# ir-sender.net
KiCad netlist of a schematic drawn in EAGLE
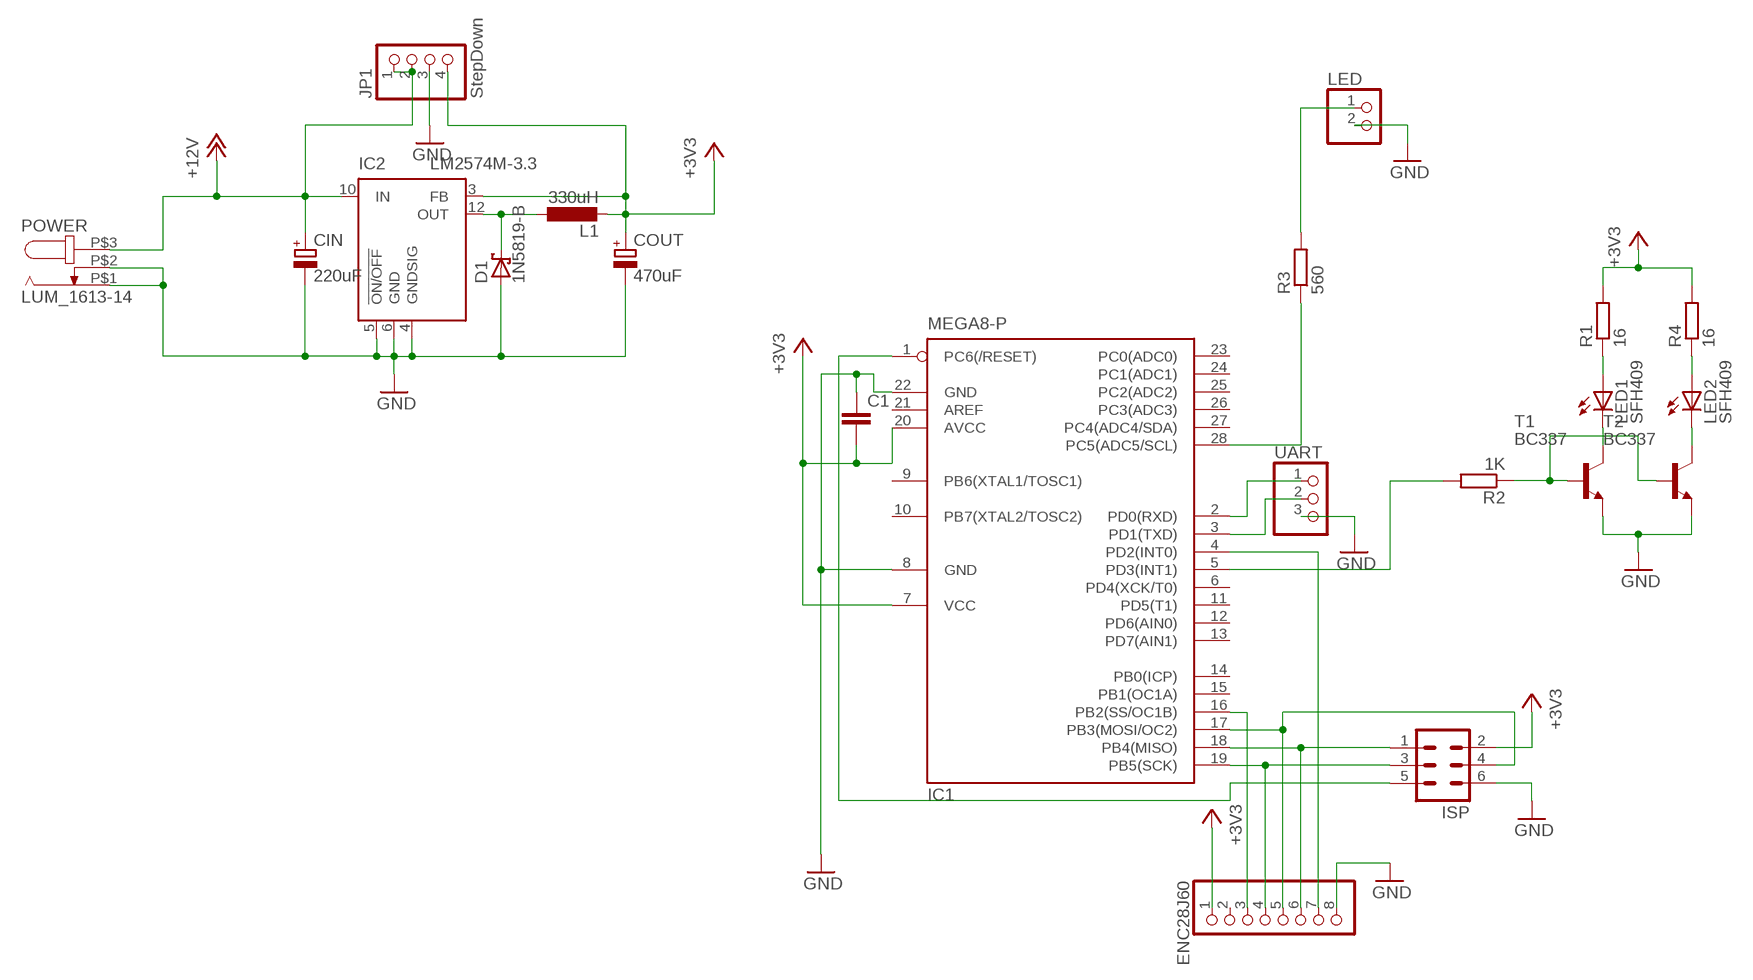
[diagram p0: schematic, sheet 1]

(export (version "E")
  (design (tool "Eeschema 10.0.6"))
  (components
    (comp (ref "C1")
      (value "C-EU025-030X050")
      (footprint "eagle-import:C025-030X050")
      (libsource (lib "eagle-import") (part "C-EU025-030X050"))
    )
    (comp (ref "CIN")
      (value "220uF")
      (footprint "eagle-import:E3,5-8")
      (libsource (lib "eagle-import") (part "CPOL-EUE3.5-8"))
    )
    (comp (ref "COUT")
      (value "470uF")
      (footprint "eagle-import:E5-10,5")
      (libsource (lib "eagle-import") (part "CPOL-EUE5-10.5"))
    )
    (comp (ref "D1")
      (value "1N5819-B")
      (footprint "eagle-import:DO41-7.6")
      (libsource (lib "eagle-import") (part "1N5819-B"))
    )
    (comp (ref "ENC28J60")
      (value "PINHD-1X8")
      (footprint "eagle-import:1X08")
      (libsource (lib "eagle-import") (part "PINHD-1X8"))
    )
    (comp (ref "IC1")
      (value "MEGA8-P")
      (footprint "eagle-import:DIL28-3")
      (libsource (lib "eagle-import") (part "MEGA8-P"))
    )
    (comp (ref "IC2")
      (value "LM2574M-3.3")
      (footprint "eagle-import:SO14W")
      (libsource (lib "eagle-import") (part "LM2574?-M3.3"))
    )
    (comp (ref "ISP")
      (value "ML6")
      (footprint "eagle-import:ML6")
      (libsource (lib "eagle-import") (part "ML6"))
    )
    (comp (ref "JP1")
      (value "StepDown")
      (footprint "eagle-import:1X04")
      (libsource (lib "eagle-import") (part "PINHD-1X4"))
    )
    (comp (ref "L1")
      (value "330uH")
      (footprint "eagle-import:PIS2816")
      (libsource (lib "eagle-import") (part "PIS4728"))
    )
    (comp (ref "LED")
      (value "PINHD-1X2")
      (footprint "eagle-import:1X02")
      (libsource (lib "eagle-import") (part "PINHD-1X2"))
    )
    (comp (ref "LED1")
      (value "SFH409")
      (footprint "eagle-import:SFH482")
      (libsource (lib "eagle-import") (part "LEDSFH482"))
    )
    (comp (ref "LED2")
      (value "SFH409")
      (footprint "eagle-import:SFH482")
      (libsource (lib "eagle-import") (part "LEDSFH482"))
    )
    (comp (ref "POWER")
      (value "LUM_1613-14")
      (footprint "eagle-import:DCJ0202")
      (libsource (lib "eagle-import") (part "LUM_1613-14"))
    )
    (comp (ref "R1")
      (value "16")
      (footprint "eagle-import:0207_7")
      (libsource (lib "eagle-import") (part "R-EU_0207/7"))
    )
    (comp (ref "R2")
      (value "1K")
      (footprint "eagle-import:0207_7")
      (libsource (lib "eagle-import") (part "R-EU_0207/7"))
    )
    (comp (ref "R3")
      (value "560")
      (footprint "eagle-import:0207_7")
      (libsource (lib "eagle-import") (part "R-EU_0207/7"))
    )
    (comp (ref "R4")
      (value "16")
      (footprint "eagle-import:0207_7")
      (libsource (lib "eagle-import") (part "R-EU_0207/7"))
    )
    (comp (ref "T1")
      (value "BC337")
      (footprint "eagle-import:TO92")
      (libsource (lib "eagle-import") (part "BC337"))
    )
    (comp (ref "T2")
      (value "BC337")
      (footprint "eagle-import:TO92")
      (libsource (lib "eagle-import") (part "BC337"))
    )
    (comp (ref "UART")
      (value "PINHD-1X3_2.54")
      (footprint "eagle-import:1X03")
      (libsource (lib "eagle-import") (part "PINHD-1X3_2.54"))
    )
  )
  (nets
    (net (code "1") (name "+3V3") (class "Default")
      (node (ref "C1") (pin "2") (pinfunction "2_2") (pintype "passive"))
      (node (ref "COUT") (pin "+") (pinfunction "+_+") (pintype "passive"))
      (node (ref "ENC28J60") (pin "1") (pinfunction "1_1") (pintype "passive"))
      (node (ref "IC1") (pin "20") (pinfunction "AVCC_20") (pintype "power_in"))
      (node (ref "IC1") (pin "7") (pinfunction "VCC_7") (pintype "power_in"))
      (node (ref "IC2") (pin "3") (pinfunction "FB_3") (pintype "input"))
      (node (ref "ISP") (pin "2") (pinfunction "2_2") (pintype "passive"))
      (node (ref "JP1") (pin "4") (pinfunction "4_4") (pintype "passive"))
      (node (ref "L1") (pin "2") (pinfunction "2_2") (pintype "passive"))
      (node (ref "R1") (pin "2") (pinfunction "2_2") (pintype "passive"))
      (node (ref "R4") (pin "2") (pinfunction "2_2") (pintype "passive"))
    )
    (net (code "2") (name "+12V") (class "Default")
      (node (ref "CIN") (pin "+") (pinfunction "+_+") (pintype "passive"))
      (node (ref "IC2") (pin "10") (pinfunction "IN_10") (pintype "input"))
      (node (ref "JP1") (pin "1") (pinfunction "1_1") (pintype "passive"))
      (node (ref "JP1") (pin "2") (pinfunction "2_2") (pintype "passive"))
      (node (ref "POWER") (pin "P$3") (pinfunction "3_P$3") (pintype "passive"))
    )
    (net (code "3") (name "GND") (class "Default")
      (node (ref "C1") (pin "1") (pinfunction "1_1") (pintype "passive"))
      (node (ref "CIN") (pin "-") (pinfunction "-_-") (pintype "passive"))
      (node (ref "COUT") (pin "-") (pinfunction "-_-") (pintype "passive"))
      (node (ref "D1") (pin "A") (pinfunction "A_A") (pintype "passive"))
      (node (ref "ENC28J60") (pin "8") (pinfunction "8_8") (pintype "passive"))
      (node (ref "IC1") (pin "22") (pinfunction "GND_22") (pintype "power_in"))
      (node (ref "IC1") (pin "8") (pinfunction "GND_8") (pintype "power_in"))
      (node (ref "IC2") (pin "4") (pinfunction "GNDSIG_4") (pintype "input"))
      (node (ref "IC2") (pin "5") (pinfunction "~{ON/OFF}_5") (pintype "input"))
      (node (ref "IC2") (pin "6") (pinfunction "GND_6") (pintype "power_in"))
      (node (ref "ISP") (pin "6") (pinfunction "6_6") (pintype "passive"))
      (node (ref "JP1") (pin "3") (pinfunction "3_3") (pintype "passive"))
      (node (ref "LED") (pin "2") (pinfunction "2_2") (pintype "passive"))
      (node (ref "POWER") (pin "P$1") (pinfunction "1_P$1") (pintype "passive"))
      (node (ref "POWER") (pin "P$2") (pinfunction "2_P$2") (pintype "passive"))
      (node (ref "T1") (pin "1") (pinfunction "E_1") (pintype "passive"))
      (node (ref "T2") (pin "1") (pinfunction "E_1") (pintype "passive"))
      (node (ref "UART") (pin "3") (pinfunction "3_3") (pintype "passive"))
    )
    (net (code "4") (name "Net-(IC1-PB2(SS{slash}OC1B))") (class "Default")
      (node (ref "ENC28J60") (pin "3") (pinfunction "3_3") (pintype "passive"))
      (node (ref "IC1") (pin "16") (pinfunction "PB2(SS/OC1B)_16") (pintype "bidirectional"))
    )
    (net (code "5") (name "Net-(IC1-PB3(MOSI{slash}OC2))") (class "Default")
      (node (ref "ENC28J60") (pin "5") (pinfunction "5_5") (pintype "passive"))
      (node (ref "IC1") (pin "17") (pinfunction "PB3(MOSI/OC2)_17") (pintype "bidirectional"))
      (node (ref "ISP") (pin "4") (pinfunction "4_4") (pintype "passive"))
    )
    (net (code "6") (name "Net-(IC1-PB4(MISO))") (class "Default")
      (node (ref "ENC28J60") (pin "6") (pinfunction "6_6") (pintype "passive"))
      (node (ref "IC1") (pin "18") (pinfunction "PB4(MISO)_18") (pintype "bidirectional"))
      (node (ref "ISP") (pin "1") (pinfunction "1_1") (pintype "passive"))
    )
    (net (code "7") (name "Net-(IC1-PB5(SCK))") (class "Default")
      (node (ref "ENC28J60") (pin "4") (pinfunction "4_4") (pintype "passive"))
      (node (ref "IC1") (pin "19") (pinfunction "PB5(SCK)_19") (pintype "bidirectional"))
      (node (ref "ISP") (pin "3") (pinfunction "3_3") (pintype "passive"))
    )
    (net (code "8") (name "Net-(IC1-PC5(ADC5{slash}SCL))") (class "Default")
      (node (ref "IC1") (pin "28") (pinfunction "PC5(ADC5/SCL)_28") (pintype "bidirectional"))
      (node (ref "R3") (pin "1") (pinfunction "1_1") (pintype "passive"))
    )
    (net (code "9") (name "Net-(IC1-PC6({slash}RESET))") (class "Default")
      (node (ref "IC1") (pin "1") (pinfunction "PC6(/RESET)_1") (pintype "bidirectional"))
      (node (ref "ISP") (pin "5") (pinfunction "5_5") (pintype "passive"))
    )
    (net (code "10") (name "Net-(IC1-PD0(RXD))") (class "Default")
      (node (ref "IC1") (pin "2") (pinfunction "PD0(RXD)_2") (pintype "bidirectional"))
      (node (ref "UART") (pin "1") (pinfunction "1_1") (pintype "passive"))
    )
    (net (code "11") (name "Net-(IC1-PD1(TXD))") (class "Default")
      (node (ref "IC1") (pin "3") (pinfunction "PD1(TXD)_3") (pintype "bidirectional"))
      (node (ref "UART") (pin "2") (pinfunction "2_2") (pintype "passive"))
    )
    (net (code "12") (name "Net-(IC1-PD2(INT0))") (class "Default")
      (node (ref "ENC28J60") (pin "7") (pinfunction "7_7") (pintype "passive"))
      (node (ref "IC1") (pin "4") (pinfunction "PD2(INT0)_4") (pintype "bidirectional"))
    )
    (net (code "13") (name "Net-(IC1-PD3(INT1))") (class "Default")
      (node (ref "IC1") (pin "5") (pinfunction "PD3(INT1)_5") (pintype "bidirectional"))
      (node (ref "R2") (pin "2") (pinfunction "2_2") (pintype "passive"))
    )
    (net (code "14") (name "Net-(IC2-OUT)") (class "Default")
      (node (ref "D1") (pin "C") (pinfunction "C_C") (pintype "passive"))
      (node (ref "IC2") (pin "12") (pinfunction "OUT_12") (pintype "passive"))
      (node (ref "L1") (pin "1") (pinfunction "1_1") (pintype "passive"))
    )
    (net (code "15") (name "Net-(LED-Pad1)") (class "Default")
      (node (ref "LED") (pin "1") (pinfunction "1_1") (pintype "passive"))
      (node (ref "R3") (pin "2") (pinfunction "2_2") (pintype "passive"))
    )
    (net (code "16") (name "Net-(LED1-C)") (class "Default")
      (node (ref "LED1") (pin "K") (pinfunction "C_K") (pintype "passive"))
      (node (ref "T1") (pin "3") (pinfunction "C_3") (pintype "passive"))
    )
    (net (code "17") (name "Net-(LED1-PadA)") (class "Default")
      (node (ref "LED1") (pin "A") (pinfunction "A_A") (pintype "passive"))
      (node (ref "R1") (pin "1") (pinfunction "1_1") (pintype "passive"))
    )
    (net (code "18") (name "Net-(LED2-C)") (class "Default")
      (node (ref "LED2") (pin "K") (pinfunction "C_K") (pintype "passive"))
      (node (ref "T2") (pin "3") (pinfunction "C_3") (pintype "passive"))
    )
    (net (code "19") (name "Net-(LED2-PadA)") (class "Default")
      (node (ref "LED2") (pin "A") (pinfunction "A_A") (pintype "passive"))
      (node (ref "R4") (pin "1") (pinfunction "1_1") (pintype "passive"))
    )
    (net (code "20") (name "Net-(T1-B)") (class "Default")
      (node (ref "R2") (pin "1") (pinfunction "1_1") (pintype "passive"))
      (node (ref "T1") (pin "2") (pinfunction "B_2") (pintype "passive"))
      (node (ref "T2") (pin "2") (pinfunction "B_2") (pintype "passive"))
    )
    (net (code "21") (name "unconnected-(ENC28J60-Pad2)") (class "Default")
      (node (ref "ENC28J60") (pin "2") (pinfunction "2_2") (pintype "passive"))
    )
    (net (code "22") (name "unconnected-(IC1-AREF-Pad21)") (class "Default")
      (node (ref "IC1") (pin "21") (pinfunction "AREF_21") (pintype "passive"))
    )
    (net (code "23") (name "unconnected-(IC1-PB0(ICP)-Pad14)") (class "Default")
      (node (ref "IC1") (pin "14") (pinfunction "PB0(ICP)_14") (pintype "bidirectional"))
    )
    (net (code "24") (name "unconnected-(IC1-PB1(OC1A)-Pad15)") (class "Default")
      (node (ref "IC1") (pin "15") (pinfunction "PB1(OC1A)_15") (pintype "bidirectional"))
    )
    (net (code "25") (name "unconnected-(IC1-PB6(XTAL1{slash}TOSC1)-Pad9)") (class "Default")
      (node (ref "IC1") (pin "9") (pinfunction "PB6(XTAL1/TOSC1)_9") (pintype "bidirectional"))
    )
    (net (code "26") (name "unconnected-(IC1-PB7(XTAL2{slash}TOSC2)-Pad10)") (class "Default")
      (node (ref "IC1") (pin "10") (pinfunction "PB7(XTAL2/TOSC2)_10") (pintype "bidirectional"))
    )
    (net (code "27") (name "unconnected-(IC1-PC0(ADC0)-Pad23)") (class "Default")
      (node (ref "IC1") (pin "23") (pinfunction "PC0(ADC0)_23") (pintype "bidirectional"))
    )
    (net (code "28") (name "unconnected-(IC1-PC1(ADC1)-Pad24)") (class "Default")
      (node (ref "IC1") (pin "24") (pinfunction "PC1(ADC1)_24") (pintype "bidirectional"))
    )
    (net (code "29") (name "unconnected-(IC1-PC2(ADC2)-Pad25)") (class "Default")
      (node (ref "IC1") (pin "25") (pinfunction "PC2(ADC2)_25") (pintype "bidirectional"))
    )
    (net (code "30") (name "unconnected-(IC1-PC3(ADC3)-Pad26)") (class "Default")
      (node (ref "IC1") (pin "26") (pinfunction "PC3(ADC3)_26") (pintype "bidirectional"))
    )
    (net (code "31") (name "unconnected-(IC1-PC4(ADC4{slash}SDA)-Pad27)") (class "Default")
      (node (ref "IC1") (pin "27") (pinfunction "PC4(ADC4/SDA)_27") (pintype "bidirectional"))
    )
    (net (code "32") (name "unconnected-(IC1-PD4(XCK{slash}T0)-Pad6)") (class "Default")
      (node (ref "IC1") (pin "6") (pinfunction "PD4(XCK/T0)_6") (pintype "bidirectional"))
    )
    (net (code "33") (name "unconnected-(IC1-PD5(T1)-Pad11)") (class "Default")
      (node (ref "IC1") (pin "11") (pinfunction "PD5(T1)_11") (pintype "bidirectional"))
    )
    (net (code "34") (name "unconnected-(IC1-PD6(AIN0)-Pad12)") (class "Default")
      (node (ref "IC1") (pin "12") (pinfunction "PD6(AIN0)_12") (pintype "bidirectional"))
    )
    (net (code "35") (name "unconnected-(IC1-PD7(AIN1)-Pad13)") (class "Default")
      (node (ref "IC1") (pin "13") (pinfunction "PD7(AIN1)_13") (pintype "bidirectional"))
    )
  )
)
